# EMI_Stage_Break_Out.net
KiCad netlist of a schematic drawn in Altium Designer
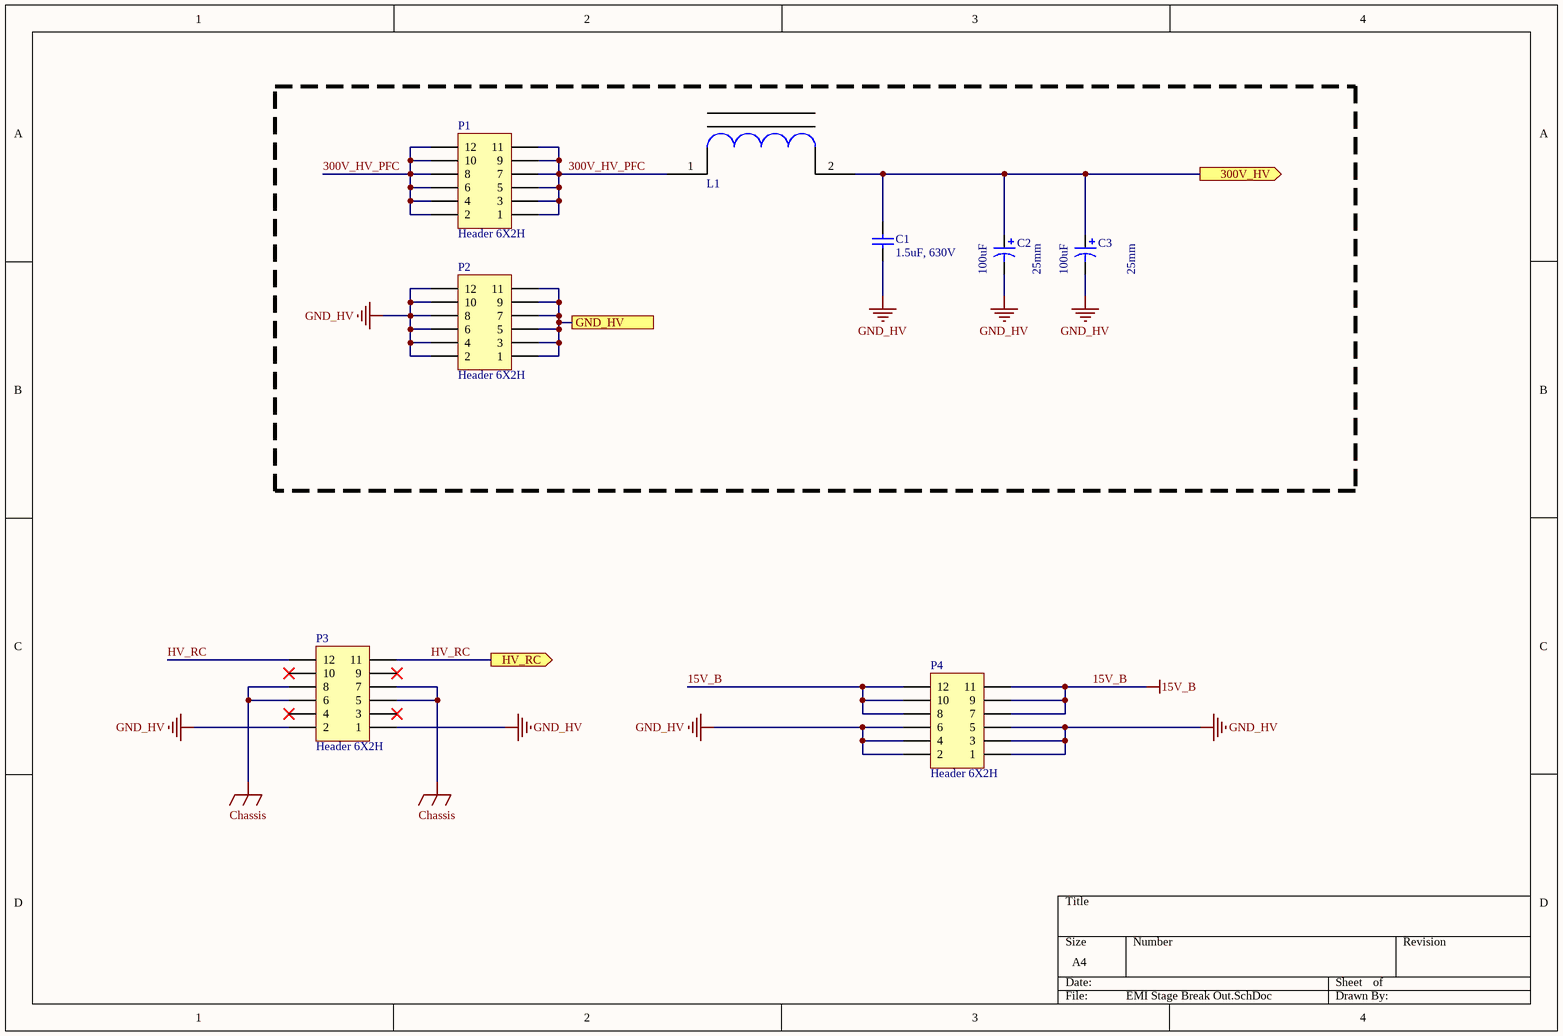
[diagram p0: EMI Stage Break Out.SchDoc]

(export (version "E")
  (design (tool "Eeschema 10.0.6"))
  (components
    (comp (ref "C1")
      (value "1.5uF, 630V")
      (footprint "L31_W15_H24.5_P27.5")
      (description "WCAP-FTBE THT Film Capacitors, 1.5uF, 630VDC")
      (fields (field (name "PART NUMBER") "890303427009CS") (field (name "PUBLISHER") "Wurth Elektronik"))
      (libsource (lib "Altium_WCAP-FTBE_rev19a") (part "890303427009CS"))
    )
    (comp (ref "C2")
      (value "25mm")
      (footprint "450V_25mm_Dia_10mm_pitch - Black")
      (description "Polarized Capacitor (Radial)")
      (fields (field (name "ALTIUM_VALUE") "100uF") (field (name "PUBLISHER") "Altium Limited"))
      (libsource (lib "Miscellaneous Devices") (part "Cap Pol1"))
    )
    (comp (ref "C3")
      (value "25mm")
      (footprint "450V_25mm_Dia_10mm_pitch - Black")
      (description "Polarized Capacitor (Radial)")
      (fields (field (name "ALTIUM_VALUE") "100uF") (field (name "PUBLISHER") "Altium Limited"))
      (libsource (lib "Miscellaneous Devices") (part "Cap Pol1"))
    )
    (comp (ref "L1")
      (value "Transformer_Inductor")
      (footprint "Shim Inductor")
      (libsource (lib "Power Board UCC28951") (part "Transformer_Inductor"))
    )
    (comp (ref "P1")
      (value "Header 6X2H")
      (footprint "Stackable-Conn")
      (description "Header, 6-Pin, Dual row, Right Angle")
      (fields (field (name "PUBLISHER") "Altium Limited"))
      (libsource (lib "Power Board UCC28951") (part "Header 6X2H"))
    )
    (comp (ref "P2")
      (value "Header 6X2H")
      (footprint "Stackable-Conn")
      (description "Header, 6-Pin, Dual row, Right Angle")
      (fields (field (name "PUBLISHER") "Altium Limited"))
      (libsource (lib "Power Board UCC28951") (part "Header 6X2H"))
    )
    (comp (ref "P3")
      (value "Header 6X2H")
      (footprint "Stackable-Conn")
      (description "Header, 6-Pin, Dual row, Right Angle")
      (fields (field (name "PUBLISHER") "Altium Limited"))
      (libsource (lib "Power Board UCC28951") (part "Header 6X2H"))
    )
    (comp (ref "P4")
      (value "Header 6X2H")
      (footprint "Stackable-Conn")
      (description "Header, 6-Pin, Dual row, Right Angle")
      (fields (field (name "PUBLISHER") "Altium Limited"))
      (libsource (lib "Power Board UCC28951") (part "Header 6X2H"))
    )
  )
  (nets
    (net (code "1") (name "/300V_HV") (class "Default")
      (node (ref "C1") (pin "2") (pinfunction "2_2") (pintype "passive"))
      (node (ref "C2") (pin "1") (pinfunction "1_1") (pintype "passive"))
      (node (ref "C3") (pin "1") (pinfunction "1_1") (pintype "passive"))
      (node (ref "L1") (pin "2") (pinfunction "2_2") (pintype "passive"))
    )
    (net (code "2") (name "/300V_HV_PFC") (class "Default")
      (node (ref "L1") (pin "1") (pinfunction "1_1") (pintype "passive"))
      (node (ref "P1") (pin "1") (pinfunction "1_1") (pintype "passive"))
      (node (ref "P1") (pin "10") (pinfunction "10_10") (pintype "passive"))
      (node (ref "P1") (pin "11") (pinfunction "11_11") (pintype "passive"))
      (node (ref "P1") (pin "12") (pinfunction "12_12") (pintype "passive"))
      (node (ref "P1") (pin "2") (pinfunction "2_2") (pintype "passive"))
      (node (ref "P1") (pin "3") (pinfunction "3_3") (pintype "passive"))
      (node (ref "P1") (pin "4") (pinfunction "4_4") (pintype "passive"))
      (node (ref "P1") (pin "5") (pinfunction "5_5") (pintype "passive"))
      (node (ref "P1") (pin "6") (pinfunction "6_6") (pintype "passive"))
      (node (ref "P1") (pin "7") (pinfunction "7_7") (pintype "passive"))
      (node (ref "P1") (pin "8") (pinfunction "8_8") (pintype "passive"))
      (node (ref "P1") (pin "9") (pinfunction "9_9") (pintype "passive"))
    )
    (net (code "3") (name "/HV_RC") (class "Default")
      (node (ref "P3") (pin "11") (pinfunction "11_11") (pintype "passive"))
      (node (ref "P3") (pin "12") (pinfunction "12_12") (pintype "passive"))
    )
    (net (code "4") (name "15V_B") (class "Default")
      (node (ref "P4") (pin "10") (pinfunction "10_10") (pintype "passive"))
      (node (ref "P4") (pin "11") (pinfunction "11_11") (pintype "passive"))
      (node (ref "P4") (pin "12") (pinfunction "12_12") (pintype "passive"))
      (node (ref "P4") (pin "7") (pinfunction "7_7") (pintype "passive"))
      (node (ref "P4") (pin "8") (pinfunction "8_8") (pintype "passive"))
      (node (ref "P4") (pin "9") (pinfunction "9_9") (pintype "passive"))
    )
    (net (code "5") (name "Chassis") (class "Default")
      (node (ref "P3") (pin "5") (pinfunction "5_5") (pintype "passive"))
      (node (ref "P3") (pin "6") (pinfunction "6_6") (pintype "passive"))
      (node (ref "P3") (pin "7") (pinfunction "7_7") (pintype "passive"))
      (node (ref "P3") (pin "8") (pinfunction "8_8") (pintype "passive"))
    )
    (net (code "6") (name "GND_HV") (class "Default")
      (node (ref "C1") (pin "1") (pinfunction "1_1") (pintype "passive"))
      (node (ref "C2") (pin "2") (pinfunction "2_2") (pintype "passive"))
      (node (ref "C3") (pin "2") (pinfunction "2_2") (pintype "passive"))
      (node (ref "P2") (pin "1") (pinfunction "1_1") (pintype "passive"))
      (node (ref "P2") (pin "10") (pinfunction "10_10") (pintype "passive"))
      (node (ref "P2") (pin "11") (pinfunction "11_11") (pintype "passive"))
      (node (ref "P2") (pin "12") (pinfunction "12_12") (pintype "passive"))
      (node (ref "P2") (pin "2") (pinfunction "2_2") (pintype "passive"))
      (node (ref "P2") (pin "3") (pinfunction "3_3") (pintype "passive"))
      (node (ref "P2") (pin "4") (pinfunction "4_4") (pintype "passive"))
      (node (ref "P2") (pin "5") (pinfunction "5_5") (pintype "passive"))
      (node (ref "P2") (pin "6") (pinfunction "6_6") (pintype "passive"))
      (node (ref "P2") (pin "7") (pinfunction "7_7") (pintype "passive"))
      (node (ref "P2") (pin "8") (pinfunction "8_8") (pintype "passive"))
      (node (ref "P2") (pin "9") (pinfunction "9_9") (pintype "passive"))
      (node (ref "P3") (pin "1") (pinfunction "1_1") (pintype "passive"))
      (node (ref "P3") (pin "2") (pinfunction "2_2") (pintype "passive"))
      (node (ref "P4") (pin "1") (pinfunction "1_1") (pintype "passive"))
      (node (ref "P4") (pin "2") (pinfunction "2_2") (pintype "passive"))
      (node (ref "P4") (pin "3") (pinfunction "3_3") (pintype "passive"))
      (node (ref "P4") (pin "4") (pinfunction "4_4") (pintype "passive"))
      (node (ref "P4") (pin "5") (pinfunction "5_5") (pintype "passive"))
      (node (ref "P4") (pin "6") (pinfunction "6_6") (pintype "passive"))
    )
    (net (code "7") (name "unconnected-(P3-Pad3)") (class "Default")
      (node (ref "P3") (pin "3") (pinfunction "3_3") (pintype "passive+no_connect"))
    )
    (net (code "8") (name "unconnected-(P3-Pad4)") (class "Default")
      (node (ref "P3") (pin "4") (pinfunction "4_4") (pintype "passive+no_connect"))
    )
    (net (code "9") (name "unconnected-(P3-Pad9)") (class "Default")
      (node (ref "P3") (pin "9") (pinfunction "9_9") (pintype "passive+no_connect"))
    )
    (net (code "10") (name "unconnected-(P3-Pad10)") (class "Default")
      (node (ref "P3") (pin "10") (pinfunction "10_10") (pintype "passive+no_connect"))
    )
  )
)
